# PowerSupply.net
KiCad netlist of a schematic drawn in Altium Designer
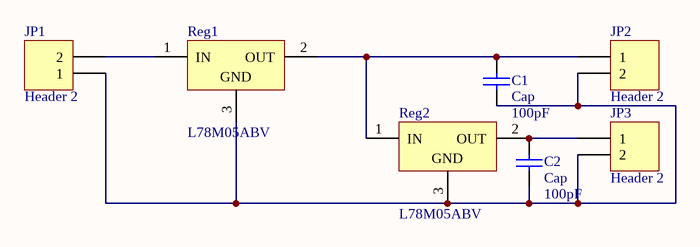
[diagram p0: PowerSupply.SCHDOC]

(export (version "E")
  (design (tool "Eeschema 10.0.6"))
  (components
    (comp (ref "C1")
      (value "Cap")
      (footprint "RAD-0.3")
      (description "Capacitor")
      (fields (field (name "ALTIUM_VALUE") "100pF") (field (name "PUBLISHER") "Altium Limited"))
      (libsource (lib "Miscellaneous Devices") (part "Cap"))
    )
    (comp (ref "C2")
      (value "Cap")
      (footprint "RAD-0.3")
      (description "Capacitor")
      (fields (field (name "ALTIUM_VALUE") "100pF") (field (name "PUBLISHER") "Altium Limited"))
      (libsource (lib "Miscellaneous Devices") (part "Cap"))
    )
    (comp (ref "JP1")
      (value "Header 2")
      (footprint "HDR1X2")
      (description "Header, 2-Pin")
      (fields (field (name "PUBLISHER") "Altium Limited"))
      (libsource (lib "") (part "Header 2_1"))
    )
    (comp (ref "JP2")
      (value "Header 2")
      (footprint "HDR1X2")
      (description "Header, 2-Pin")
      (fields (field (name "PUBLISHER") "Altium Limited"))
      (libsource (lib "Miscellaneous Connectors") (part "Header 2"))
    )
    (comp (ref "JP3")
      (value "Header 2")
      (footprint "HDR1X2")
      (description "Header, 2-Pin")
      (fields (field (name "PUBLISHER") "Altium Limited"))
      (libsource (lib "Miscellaneous Connectors") (part "Header 2"))
    )
    (comp (ref "Reg1")
      (value "L78M05ABV")
      (footprint "TO220V")
      (description "Precision 500mA Regulator")
      (fields (field (name "PUBLISHER") "Altium Limited"))
      (libsource (lib "ST Power Mgt Voltage Regulator") (part "L78M05ABV"))
    )
    (comp (ref "Reg2")
      (value "L78M05ABV")
      (footprint "TO220V")
      (description "Precision 500mA Regulator")
      (fields (field (name "PUBLISHER") "Altium Limited"))
      (libsource (lib "ST Power Mgt Voltage Regulator") (part "L78M05ABV"))
    )
  )
  (nets
    (net (code "1") (name "Net-(Reg1-GND)") (class "Default")
      (node (ref "C1") (pin "1") (pinfunction "1_1") (pintype "passive"))
      (node (ref "C2") (pin "1") (pinfunction "1_1") (pintype "passive"))
      (node (ref "JP1") (pin "1") (pinfunction "1_1") (pintype "passive"))
      (node (ref "JP2") (pin "2") (pinfunction "2_2") (pintype "passive"))
      (node (ref "JP3") (pin "2") (pinfunction "2_2") (pintype "passive"))
      (node (ref "Reg1") (pin "3") (pinfunction "GND_3") (pintype "power_in"))
      (node (ref "Reg2") (pin "3") (pinfunction "GND_3") (pintype "power_in"))
    )
    (net (code "2") (name "Net-(Reg1-IN)") (class "Default")
      (node (ref "JP1") (pin "2") (pinfunction "2_2") (pintype "passive"))
      (node (ref "Reg1") (pin "1") (pinfunction "IN_1") (pintype "power_in"))
    )
    (net (code "3") (name "Net-(Reg1-OUT)") (class "Default")
      (node (ref "C1") (pin "2") (pinfunction "2_2") (pintype "passive"))
      (node (ref "JP2") (pin "1") (pinfunction "1_1") (pintype "passive"))
      (node (ref "Reg1") (pin "2") (pinfunction "OUT_2") (pintype "power_in"))
      (node (ref "Reg2") (pin "1") (pinfunction "IN_1") (pintype "power_in"))
    )
    (net (code "4") (name "Net-(Reg2-OUT)") (class "Default")
      (node (ref "C2") (pin "2") (pinfunction "2_2") (pintype "passive"))
      (node (ref "JP3") (pin "1") (pinfunction "1_1") (pintype "passive"))
      (node (ref "Reg2") (pin "2") (pinfunction "OUT_2") (pintype "power_in"))
    )
  )
)
